# NIC_DP83848.net
KiCad netlist of a schematic drawn in Altium Designer
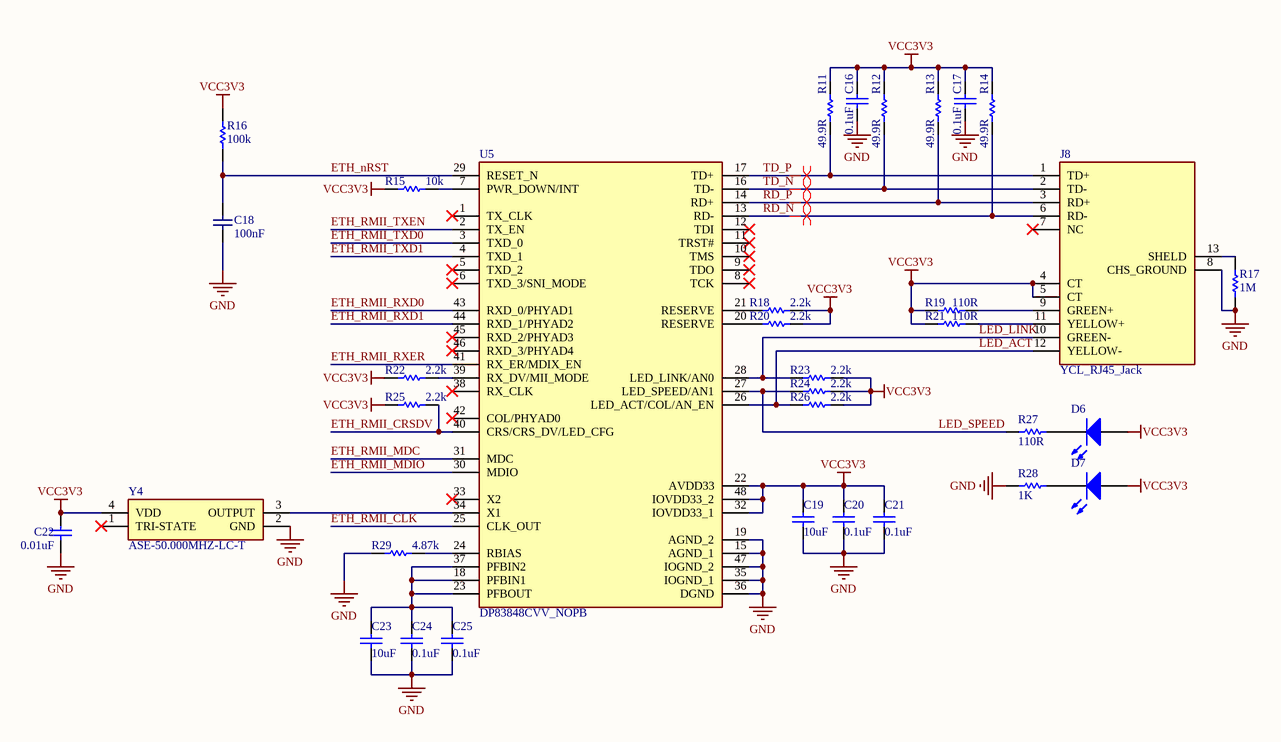
[diagram p0: NIC_DP83848.SchDoc]

(export (version "E")
  (design (tool "Eeschema 10.0.6"))
  (components
    (comp (ref "C16")
      (value "0.1uF")
      (footprint "SMD0603")
      (description "Capacitor (Semiconductor SIM Model)")
      (fields (field (name "PUBLISHER") "Altium Limited"))
      (libsource (lib "Miscellaneous Devices") (part "Cap Semi"))
    )
    (comp (ref "C17")
      (value "0.1uF")
      (footprint "SMD0603")
      (description "Capacitor (Semiconductor SIM Model)")
      (fields (field (name "PUBLISHER") "Altium Limited"))
      (libsource (lib "Miscellaneous Devices") (part "Cap Semi"))
    )
    (comp (ref "C18")
      (value "100nF")
      (footprint "SMD0603")
      (description "Capacitor (Semiconductor SIM Model)")
      (libsource (lib "SRV8") (part "Cap"))
    )
    (comp (ref "C19")
      (value "10uF")
      (footprint "SMD0603")
      (description "Capacitor (Semiconductor SIM Model)")
      (fields (field (name "PUBLISHER") "Altium Limited"))
      (libsource (lib "Miscellaneous Devices") (part "Cap Semi"))
    )
    (comp (ref "C20")
      (value "0.1uF")
      (footprint "SMD0603")
      (description "Capacitor (Semiconductor SIM Model)")
      (fields (field (name "PUBLISHER") "Altium Limited"))
      (libsource (lib "Miscellaneous Devices") (part "Cap Semi"))
    )
    (comp (ref "C21")
      (value "0.1uF")
      (footprint "SMD0603")
      (description "Capacitor (Semiconductor SIM Model)")
      (fields (field (name "PUBLISHER") "Altium Limited"))
      (libsource (lib "Miscellaneous Devices") (part "Cap Semi"))
    )
    (comp (ref "C22")
      (value "0.01uF")
      (footprint "SMD0603")
      (description "Capacitor (Semiconductor SIM Model)")
      (fields (field (name "Comment") "0.1uF") (field (name "PUBLISHER") "Altium Limited"))
      (libsource (lib "Miscellaneous Devices") (part "Cap Semi"))
    )
    (comp (ref "C23")
      (value "10uF")
      (footprint "SMD0603")
      (description "Capacitor (Semiconductor SIM Model)")
      (fields (field (name "PUBLISHER") "Altium Limited"))
      (libsource (lib "Miscellaneous Devices") (part "Cap Semi"))
    )
    (comp (ref "C24")
      (value "0.1uF")
      (footprint "SMD0603")
      (description "Capacitor (Semiconductor SIM Model)")
      (fields (field (name "PUBLISHER") "Altium Limited"))
      (libsource (lib "Miscellaneous Devices") (part "Cap Semi"))
    )
    (comp (ref "C25")
      (value "0.1uF")
      (footprint "SMD0603")
      (description "Capacitor (Semiconductor SIM Model)")
      (fields (field (name "PUBLISHER") "Altium Limited"))
      (libsource (lib "Miscellaneous Devices") (part "Cap Semi"))
    )
    (comp (ref "D6")
      (value "LED0")
      (footprint "SMD0603_LED")
      (description "Typical INFRARED GaAs LED")
      (fields (field (name "PUBLISHER") "Altium Limited"))
      (libsource (lib "Miscellaneous Devices") (part "LED0"))
    )
    (comp (ref "D7")
      (value "LED0")
      (footprint "SMD0603_LED")
      (description "Typical INFRARED GaAs LED")
      (fields (field (name "PUBLISHER") "Altium Limited"))
      (libsource (lib "Miscellaneous Devices") (part "LED0"))
    )
    (comp (ref "J8")
      (value "YCL_RJ45_Jack")
      (footprint "YCL_RJ45_Jack")
      (description "Connector")
      (fields (field (name "MANUFACTURER_PART_NUMBER") "J0011D21BNL"))
      (libsource (lib "ether_phy_lib") (part "YCL_RJ45_Jack"))
    )
    (comp (ref "R11")
      (value "49.9R")
      (footprint "SMD0603")
      (description "Semiconductor Resistor")
      (fields (field (name "PUBLISHER") "Altium Limited"))
      (libsource (lib "Miscellaneous Devices") (part "Res Semi"))
    )
    (comp (ref "R12")
      (value "49.9R")
      (footprint "SMD0603")
      (description "Semiconductor Resistor")
      (fields (field (name "PUBLISHER") "Altium Limited"))
      (libsource (lib "Miscellaneous Devices") (part "Res Semi"))
    )
    (comp (ref "R13")
      (value "49.9R")
      (footprint "SMD0603")
      (description "Semiconductor Resistor")
      (fields (field (name "PUBLISHER") "Altium Limited"))
      (libsource (lib "Miscellaneous Devices") (part "Res Semi"))
    )
    (comp (ref "R14")
      (value "49.9R")
      (footprint "SMD0603")
      (description "Semiconductor Resistor")
      (fields (field (name "PUBLISHER") "Altium Limited"))
      (libsource (lib "Miscellaneous Devices") (part "Res Semi"))
    )
    (comp (ref "R15")
      (value "10k")
      (footprint "SMD0603")
      (description "Semiconductor Resistor")
      (fields (field (name "PUBLISHER") "Altium Limited"))
      (libsource (lib "Miscellaneous Devices") (part "Res Semi"))
    )
    (comp (ref "R16")
      (value "100k")
      (footprint "SMD0603")
      (description "Semiconductor Resistor")
      (fields (field (name "Comment") "100K"))
      (libsource (lib "*") (part "Res"))
    )
    (comp (ref "R17")
      (value "1M")
      (footprint "SMD0603")
      (description "Semiconductor Resistor")
      (fields (field (name "PUBLISHER") "Altium Limited"))
      (libsource (lib "Miscellaneous Devices") (part "Res Semi"))
    )
    (comp (ref "R18")
      (value "2.2k")
      (footprint "SMD0603")
      (description "Semiconductor Resistor")
      (fields (field (name "PUBLISHER") "Altium Limited"))
      (libsource (lib "Miscellaneous Devices") (part "Res Semi"))
    )
    (comp (ref "R19")
      (value "110R")
      (footprint "SMD0603")
      (description "Semiconductor Resistor")
      (fields (field (name "PUBLISHER") "Altium Limited"))
      (libsource (lib "Miscellaneous Devices") (part "Res Semi"))
    )
    (comp (ref "R20")
      (value "2.2k")
      (footprint "SMD0603")
      (description "Semiconductor Resistor")
      (fields (field (name "PUBLISHER") "Altium Limited"))
      (libsource (lib "Miscellaneous Devices") (part "Res Semi"))
    )
    (comp (ref "R21")
      (value "110R")
      (footprint "SMD0603")
      (description "Semiconductor Resistor")
      (fields (field (name "PUBLISHER") "Altium Limited"))
      (libsource (lib "Miscellaneous Devices") (part "Res Semi"))
    )
    (comp (ref "R22")
      (value "2.2k")
      (footprint "SMD0603")
      (description "Semiconductor Resistor")
      (fields (field (name "PUBLISHER") "Altium Limited"))
      (libsource (lib "Miscellaneous Devices") (part "Res Semi"))
    )
    (comp (ref "R23")
      (value "2.2k")
      (footprint "SMD0603")
      (description "Semiconductor Resistor")
      (fields (field (name "PUBLISHER") "Altium Limited"))
      (libsource (lib "Miscellaneous Devices") (part "Res Semi"))
    )
    (comp (ref "R24")
      (value "2.2k")
      (footprint "SMD0603")
      (description "Semiconductor Resistor")
      (fields (field (name "PUBLISHER") "Altium Limited"))
      (libsource (lib "Miscellaneous Devices") (part "Res Semi"))
    )
    (comp (ref "R25")
      (value "2.2k")
      (footprint "SMD0603")
      (description "Semiconductor Resistor")
      (fields (field (name "PUBLISHER") "Altium Limited"))
      (libsource (lib "Miscellaneous Devices") (part "Res Semi"))
    )
    (comp (ref "R26")
      (value "2.2k")
      (footprint "SMD0603")
      (description "Semiconductor Resistor")
      (fields (field (name "PUBLISHER") "Altium Limited"))
      (libsource (lib "Miscellaneous Devices") (part "Res Semi"))
    )
    (comp (ref "R27")
      (value "110R")
      (footprint "SMD0603")
      (description "Semiconductor Resistor")
      (fields (field (name "Comment") "1K") (field (name "PUBLISHER") "Altium Limited"))
      (libsource (lib "Miscellaneous Devices") (part "Res Semi"))
    )
    (comp (ref "R28")
      (value "1K")
      (footprint "SMD0603")
      (description "Semiconductor Resistor")
      (fields (field (name "PUBLISHER") "Altium Limited"))
      (libsource (lib "Miscellaneous Devices") (part "Res Semi"))
    )
    (comp (ref "R29")
      (value "4.87k")
      (footprint "SMD0603")
      (description "Semiconductor Resistor")
      (fields (field (name "PUBLISHER") "Altium Limited"))
      (libsource (lib "Miscellaneous Devices") (part "Res Semi"))
    )
    (comp (ref "U5")
      (value "DP83848CVV_NOPB")
      (footprint "QFP50P900X900X160-48N")
      (description "Ethernet phy")
      (libsource (lib "ether_phy_lib") (part "DP83848CVV"))
    )
    (comp (ref "Y4")
      (value "ASE-50.000MHZ-LC-T")
      (footprint "OSC3225")
      (description "Crystal or Oscillator")
      (fields (field (name "MOUSER2 PART NUMBER") "815-ASE50.000MHZLCT"))
      (libsource (lib "ether_phy_lib") (part "ASE-50.000MHZ-LC-T"))
    )
  )
  (nets
    (net (code "1") (name "/ETH_RMII_CLK") (class "Default")
      (node (ref "U5") (pin "25") (pinfunction "CLK_OUT_25") (pintype "passive"))
    )
    (net (code "2") (name "/ETH_RMII_CRSDV") (class "Default")
      (node (ref "R25") (pin "1") (pinfunction "1_1") (pintype "passive"))
      (node (ref "U5") (pin "40") (pinfunction "CRS/CRS_DV/LED_CFG_40") (pintype "passive"))
    )
    (net (code "3") (name "/ETH_RMII_MDC") (class "Default")
      (node (ref "U5") (pin "31") (pinfunction "MDC_31") (pintype "passive"))
    )
    (net (code "4") (name "/ETH_RMII_MDIO") (class "Default")
      (node (ref "U5") (pin "30") (pinfunction "MDIO_30") (pintype "passive"))
    )
    (net (code "5") (name "/ETH_RMII_RXD0") (class "Default")
      (node (ref "U5") (pin "43") (pinfunction "RXD_0/PHYAD1_43") (pintype "passive"))
    )
    (net (code "6") (name "/ETH_RMII_RXD1") (class "Default")
      (node (ref "U5") (pin "44") (pinfunction "RXD_1/PHYAD2_44") (pintype "passive"))
    )
    (net (code "7") (name "/ETH_RMII_RXER") (class "Default")
      (node (ref "U5") (pin "41") (pinfunction "RX_ER/MDIX_EN_41") (pintype "passive"))
    )
    (net (code "8") (name "/ETH_RMII_TXD0") (class "Default")
      (node (ref "U5") (pin "3") (pinfunction "TXD_0_3") (pintype "passive"))
    )
    (net (code "9") (name "/ETH_RMII_TXD1") (class "Default")
      (node (ref "U5") (pin "4") (pinfunction "TXD_1_4") (pintype "passive"))
    )
    (net (code "10") (name "/ETH_RMII_TXEN") (class "Default")
      (node (ref "U5") (pin "2") (pinfunction "TX_EN_2") (pintype "passive"))
    )
    (net (code "11") (name "/ETH_nRST") (class "Default")
      (node (ref "C18") (pin "2") (pinfunction "2_2") (pintype "passive"))
      (node (ref "R16") (pin "1") (pinfunction "1_1") (pintype "passive"))
      (node (ref "U5") (pin "29") (pinfunction "RESET_N_29") (pintype "passive"))
    )
    (net (code "12") (name "/LED_ACT") (class "Default")
      (node (ref "J8") (pin "12") (pinfunction "YELLOW-_12") (pintype "passive"))
      (node (ref "R26") (pin "2") (pinfunction "2_2") (pintype "passive"))
      (node (ref "U5") (pin "26") (pinfunction "LED_ACT/COL/AN_EN_26") (pintype "passive"))
    )
    (net (code "13") (name "/LED_LINK") (class "Default")
      (node (ref "J8") (pin "10") (pinfunction "GREEN-_10") (pintype "passive"))
      (node (ref "R23") (pin "2") (pinfunction "2_2") (pintype "passive"))
      (node (ref "U5") (pin "28") (pinfunction "LED_LINK/AN0_28") (pintype "passive"))
    )
    (net (code "14") (name "/LED_SPEED") (class "Default")
      (node (ref "R24") (pin "1") (pinfunction "1_1") (pintype "passive"))
      (node (ref "R27") (pin "1") (pinfunction "1_1") (pintype "passive"))
      (node (ref "U5") (pin "27") (pinfunction "LED_SPEED/AN1_27") (pintype "passive"))
    )
    (net (code "15") (name "/RD_N") (class "Default")
      (node (ref "J8") (pin "6") (pinfunction "RD-_6") (pintype "passive"))
      (node (ref "R14") (pin "2") (pinfunction "2_2") (pintype "passive"))
      (node (ref "U5") (pin "13") (pinfunction "RD-_13") (pintype "passive"))
    )
    (net (code "16") (name "/RD_P") (class "Default")
      (node (ref "J8") (pin "3") (pinfunction "RD+_3") (pintype "passive"))
      (node (ref "R13") (pin "2") (pinfunction "2_2") (pintype "passive"))
      (node (ref "U5") (pin "14") (pinfunction "RD+_14") (pintype "passive"))
    )
    (net (code "17") (name "/TD_N") (class "Default")
      (node (ref "J8") (pin "2") (pinfunction "TD-_2") (pintype "passive"))
      (node (ref "R12") (pin "2") (pinfunction "2_2") (pintype "passive"))
      (node (ref "U5") (pin "16") (pinfunction "TD-_16") (pintype "passive"))
    )
    (net (code "18") (name "/TD_P") (class "Default")
      (node (ref "J8") (pin "1") (pinfunction "TD+_1") (pintype "passive"))
      (node (ref "R11") (pin "2") (pinfunction "2_2") (pintype "passive"))
      (node (ref "U5") (pin "17") (pinfunction "TD+_17") (pintype "passive"))
    )
    (net (code "19") (name "GND") (class "Default")
      (node (ref "C16") (pin "2") (pinfunction "2_2") (pintype "passive"))
      (node (ref "C17") (pin "2") (pinfunction "2_2") (pintype "passive"))
      (node (ref "C18") (pin "1") (pinfunction "1_1") (pintype "passive"))
      (node (ref "C19") (pin "2") (pinfunction "2_2") (pintype "passive"))
      (node (ref "C20") (pin "2") (pinfunction "2_2") (pintype "passive"))
      (node (ref "C21") (pin "2") (pinfunction "2_2") (pintype "passive"))
      (node (ref "C22") (pin "2") (pinfunction "2_2") (pintype "passive"))
      (node (ref "C23") (pin "2") (pinfunction "2_2") (pintype "passive"))
      (node (ref "C24") (pin "2") (pinfunction "2_2") (pintype "passive"))
      (node (ref "C25") (pin "2") (pinfunction "2_2") (pintype "passive"))
      (node (ref "J8") (pin "8") (pinfunction "CHS_GROUND_8") (pintype "passive"))
      (node (ref "R17") (pin "1") (pinfunction "1_1") (pintype "passive"))
      (node (ref "R28") (pin "1") (pinfunction "1_1") (pintype "passive"))
      (node (ref "R29") (pin "2") (pinfunction "2_2") (pintype "passive"))
      (node (ref "U5") (pin "15") (pinfunction "AGND_1_15") (pintype "passive"))
      (node (ref "U5") (pin "19") (pinfunction "AGND_2_19") (pintype "passive"))
      (node (ref "U5") (pin "35") (pinfunction "IOGND_1_35") (pintype "passive"))
      (node (ref "U5") (pin "36") (pinfunction "DGND_36") (pintype "passive"))
      (node (ref "U5") (pin "47") (pinfunction "IOGND_2_47") (pintype "passive"))
      (node (ref "Y4") (pin "2") (pinfunction "GND_2") (pintype "passive"))
    )
    (net (code "20") (name "Net-(D6-K)") (class "Default")
      (node (ref "D6") (pin "2") (pinfunction "K_2") (pintype "passive"))
      (node (ref "R27") (pin "2") (pinfunction "2_2") (pintype "passive"))
    )
    (net (code "21") (name "Net-(D7-K)") (class "Default")
      (node (ref "D7") (pin "2") (pinfunction "K_2") (pintype "passive"))
      (node (ref "R28") (pin "2") (pinfunction "2_2") (pintype "passive"))
    )
    (net (code "22") (name "Net-(J8-GREEN+)") (class "Default")
      (node (ref "J8") (pin "9") (pinfunction "GREEN+_9") (pintype "passive"))
      (node (ref "R19") (pin "2") (pinfunction "2_2") (pintype "passive"))
    )
    (net (code "23") (name "Net-(J8-SHELD)") (class "Default")
      (node (ref "J8") (pin "13") (pinfunction "SHELD_13") (pintype "passive"))
      (node (ref "R17") (pin "2") (pinfunction "2_2") (pintype "passive"))
    )
    (net (code "24") (name "Net-(J8-YELLOW+)") (class "Default")
      (node (ref "J8") (pin "11") (pinfunction "YELLOW+_11") (pintype "passive"))
      (node (ref "R21") (pin "2") (pinfunction "2_2") (pintype "passive"))
    )
    (net (code "25") (name "Net-(R18-Pad2)") (class "Default")
      (node (ref "R18") (pin "2") (pinfunction "2_2") (pintype "passive"))
      (node (ref "U5") (pin "21") (pinfunction "RESERVE_21") (pintype "passive"))
    )
    (net (code "26") (name "Net-(R20-Pad1)") (class "Default")
      (node (ref "R20") (pin "1") (pinfunction "1_1") (pintype "passive"))
      (node (ref "U5") (pin "20") (pinfunction "RESERVE_20") (pintype "passive"))
    )
    (net (code "27") (name "Net-(U5-PFBIN1)") (class "Default")
      (node (ref "C23") (pin "1") (pinfunction "1_1") (pintype "passive"))
      (node (ref "C24") (pin "1") (pinfunction "1_1") (pintype "passive"))
      (node (ref "C25") (pin "1") (pinfunction "1_1") (pintype "passive"))
      (node (ref "U5") (pin "18") (pinfunction "PFBIN1_18") (pintype "passive"))
      (node (ref "U5") (pin "23") (pinfunction "PFBOUT_23") (pintype "passive"))
      (node (ref "U5") (pin "37") (pinfunction "PFBIN2_37") (pintype "passive"))
    )
    (net (code "28") (name "Net-(U5-PWR_DOWN{slash}INT)") (class "Default")
      (node (ref "R15") (pin "1") (pinfunction "1_1") (pintype "passive"))
      (node (ref "U5") (pin "7") (pinfunction "PWR_DOWN/INT_7") (pintype "passive"))
    )
    (net (code "29") (name "Net-(U5-RBIAS)") (class "Default")
      (node (ref "R29") (pin "1") (pinfunction "1_1") (pintype "passive"))
      (node (ref "U5") (pin "24") (pinfunction "RBIAS_24") (pintype "passive"))
    )
    (net (code "30") (name "Net-(U5-RX_DV{slash}MII_MODE)") (class "Default")
      (node (ref "R22") (pin "1") (pinfunction "1_1") (pintype "passive"))
      (node (ref "U5") (pin "39") (pinfunction "RX_DV/MII_MODE_39") (pintype "passive"))
    )
    (net (code "31") (name "Net-(U5-X1)") (class "Default")
      (node (ref "U5") (pin "34") (pinfunction "X1_34") (pintype "passive"))
      (node (ref "Y4") (pin "3") (pinfunction "OUTPUT_3") (pintype "passive"))
    )
    (net (code "32") (name "VCC3V3") (class "Default")
      (node (ref "C16") (pin "1") (pinfunction "1_1") (pintype "passive"))
      (node (ref "C17") (pin "1") (pinfunction "1_1") (pintype "passive"))
      (node (ref "C19") (pin "1") (pinfunction "1_1") (pintype "passive"))
      (node (ref "C20") (pin "1") (pinfunction "1_1") (pintype "passive"))
      (node (ref "C21") (pin "1") (pinfunction "1_1") (pintype "passive"))
      (node (ref "C22") (pin "1") (pinfunction "1_1") (pintype "passive"))
      (node (ref "D6") (pin "1") (pinfunction "A_1") (pintype "passive"))
      (node (ref "D7") (pin "1") (pinfunction "A_1") (pintype "passive"))
      (node (ref "J8") (pin "4") (pinfunction "CT_4") (pintype "passive"))
      (node (ref "J8") (pin "5") (pinfunction "CT_5") (pintype "passive"))
      (node (ref "R11") (pin "1") (pinfunction "1_1") (pintype "passive"))
      (node (ref "R12") (pin "1") (pinfunction "1_1") (pintype "passive"))
      (node (ref "R13") (pin "1") (pinfunction "1_1") (pintype "passive"))
      (node (ref "R14") (pin "1") (pinfunction "1_1") (pintype "passive"))
      (node (ref "R15") (pin "2") (pinfunction "2_2") (pintype "passive"))
      (node (ref "R16") (pin "2") (pinfunction "2_2") (pintype "passive"))
      (node (ref "R18") (pin "1") (pinfunction "1_1") (pintype "passive"))
      (node (ref "R19") (pin "1") (pinfunction "1_1") (pintype "passive"))
      (node (ref "R20") (pin "2") (pinfunction "2_2") (pintype "passive"))
      (node (ref "R21") (pin "1") (pinfunction "1_1") (pintype "passive"))
      (node (ref "R22") (pin "2") (pinfunction "2_2") (pintype "passive"))
      (node (ref "R23") (pin "1") (pinfunction "1_1") (pintype "passive"))
      (node (ref "R24") (pin "2") (pinfunction "2_2") (pintype "passive"))
      (node (ref "R25") (pin "2") (pinfunction "2_2") (pintype "passive"))
      (node (ref "R26") (pin "1") (pinfunction "1_1") (pintype "passive"))
      (node (ref "U5") (pin "22") (pinfunction "AVDD33_22") (pintype "passive"))
      (node (ref "U5") (pin "32") (pinfunction "IOVDD33_1_32") (pintype "passive"))
      (node (ref "U5") (pin "48") (pinfunction "IOVDD33_2_48") (pintype "passive"))
      (node (ref "Y4") (pin "4") (pinfunction "VDD_4") (pintype "passive"))
    )
    (net (code "33") (name "unconnected-(J8-NC-Pad7)") (class "Default")
      (node (ref "J8") (pin "7") (pinfunction "NC_7") (pintype "passive+no_connect"))
    )
    (net (code "34") (name "unconnected-(U5-COL{slash}PHYAD0-Pad42)") (class "Default")
      (node (ref "U5") (pin "42") (pinfunction "COL/PHYAD0_42") (pintype "passive+no_connect"))
    )
    (net (code "35") (name "unconnected-(U5-RXD_2{slash}PHYAD3-Pad45)") (class "Default")
      (node (ref "U5") (pin "45") (pinfunction "RXD_2/PHYAD3_45") (pintype "passive+no_connect"))
    )
    (net (code "36") (name "unconnected-(U5-RXD_3{slash}PHYAD4-Pad46)") (class "Default")
      (node (ref "U5") (pin "46") (pinfunction "RXD_3/PHYAD4_46") (pintype "passive+no_connect"))
    )
    (net (code "37") (name "unconnected-(U5-RX_CLK-Pad38)") (class "Default")
      (node (ref "U5") (pin "38") (pinfunction "RX_CLK_38") (pintype "passive+no_connect"))
    )
    (net (code "38") (name "unconnected-(U5-TCK-Pad8)") (class "Default")
      (node (ref "U5") (pin "8") (pinfunction "TCK_8") (pintype "passive+no_connect"))
    )
    (net (code "39") (name "unconnected-(U5-TDI-Pad12)") (class "Default")
      (node (ref "U5") (pin "12") (pinfunction "TDI_12") (pintype "passive+no_connect"))
    )
    (net (code "40") (name "unconnected-(U5-TDO-Pad9)") (class "Default")
      (node (ref "U5") (pin "9") (pinfunction "TDO_9") (pintype "passive+no_connect"))
    )
    (net (code "41") (name "unconnected-(U5-TMS-Pad10)") (class "Default")
      (node (ref "U5") (pin "10") (pinfunction "TMS_10") (pintype "passive+no_connect"))
    )
    (net (code "42") (name "unconnected-(U5-TRST#-Pad11)") (class "Default")
      (node (ref "U5") (pin "11") (pinfunction "TRST#_11") (pintype "passive+no_connect"))
    )
    (net (code "43") (name "unconnected-(U5-TXD_2-Pad5)") (class "Default")
      (node (ref "U5") (pin "5") (pinfunction "TXD_2_5") (pintype "passive+no_connect"))
    )
    (net (code "44") (name "unconnected-(U5-TXD_3{slash}SNI_MODE-Pad6)") (class "Default")
      (node (ref "U5") (pin "6") (pinfunction "TXD_3/SNI_MODE_6") (pintype "passive+no_connect"))
    )
    (net (code "45") (name "unconnected-(U5-TX_CLK-Pad1)") (class "Default")
      (node (ref "U5") (pin "1") (pinfunction "TX_CLK_1") (pintype "passive+no_connect"))
    )
    (net (code "46") (name "unconnected-(U5-X2-Pad33)") (class "Default")
      (node (ref "U5") (pin "33") (pinfunction "X2_33") (pintype "passive+no_connect"))
    )
    (net (code "47") (name "unconnected-(Y4-TRI-STATE-Pad1)") (class "Default")
      (node (ref "Y4") (pin "1") (pinfunction "TRI-STATE_1") (pintype "passive+no_connect"))
    )
  )
)
